# Reset_With_Power_On.net
KiCad netlist of a schematic drawn in Altium Designer
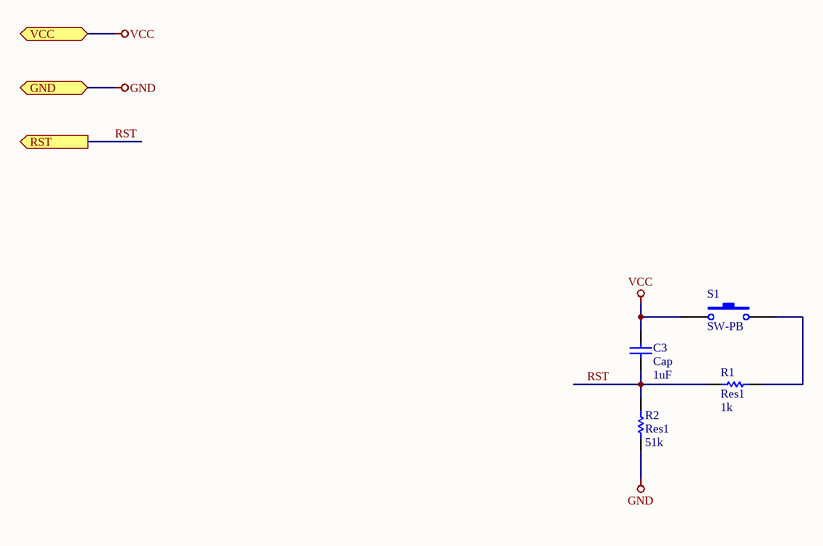
[diagram p0: Reset_With_Power_On.SchDoc]

(export (version "E")
  (design (tool "Eeschema 10.0.6"))
  (components
    (comp (ref "C3")
      (value "Cap")
      (footprint "C0805")
      (description "Non-Polar Capacitor")
      (fields (field (name "ALTIUM_VALUE") "1uF"))
      (libsource (lib "Integrated_Library") (part "Cap"))
    )
    (comp (ref "R1")
      (value "Res1")
      (footprint "R0805")
      (description "Resistor")
      (fields (field (name "ALTIUM_VALUE") "1k"))
      (libsource (lib "Integrated_Library") (part "Res1"))
    )
    (comp (ref "R2")
      (value "Res1")
      (footprint "R0805")
      (description "Resistor")
      (fields (field (name "ALTIUM_VALUE") "51k"))
      (libsource (lib "Integrated_Library") (part "Res1"))
    )
    (comp (ref "S1")
      (value "SW-PB")
      (footprint "KEY-DIP4")
      (description "Switch")
      (libsource (lib "Integrated_Library") (part "SW-PB"))
    )
  )
  (nets
    (net (code "1") (name "/RST") (class "Default")
      (node (ref "C3") (pin "2") (pinfunction "2_2") (pintype "passive"))
      (node (ref "R1") (pin "1") (pinfunction "1_1") (pintype "passive"))
      (node (ref "R2") (pin "2") (pinfunction "2_2") (pintype "passive"))
    )
    (net (code "2") (name "GND") (class "Default")
      (node (ref "R2") (pin "1") (pinfunction "1_1") (pintype "passive"))
    )
    (net (code "3") (name "Net-(R1-Pad2)") (class "Default")
      (node (ref "R1") (pin "2") (pinfunction "2_2") (pintype "passive"))
      (node (ref "S1") (pin "2") (pinfunction "2_2") (pintype "passive"))
    )
    (net (code "4") (name "VCC") (class "Default")
      (node (ref "C3") (pin "1") (pinfunction "1_1") (pintype "passive"))
      (node (ref "S1") (pin "1") (pinfunction "1_1") (pintype "passive"))
    )
  )
)
